# myfly.net
KiCad netlist of a schematic drawn in EasyEDA Pro
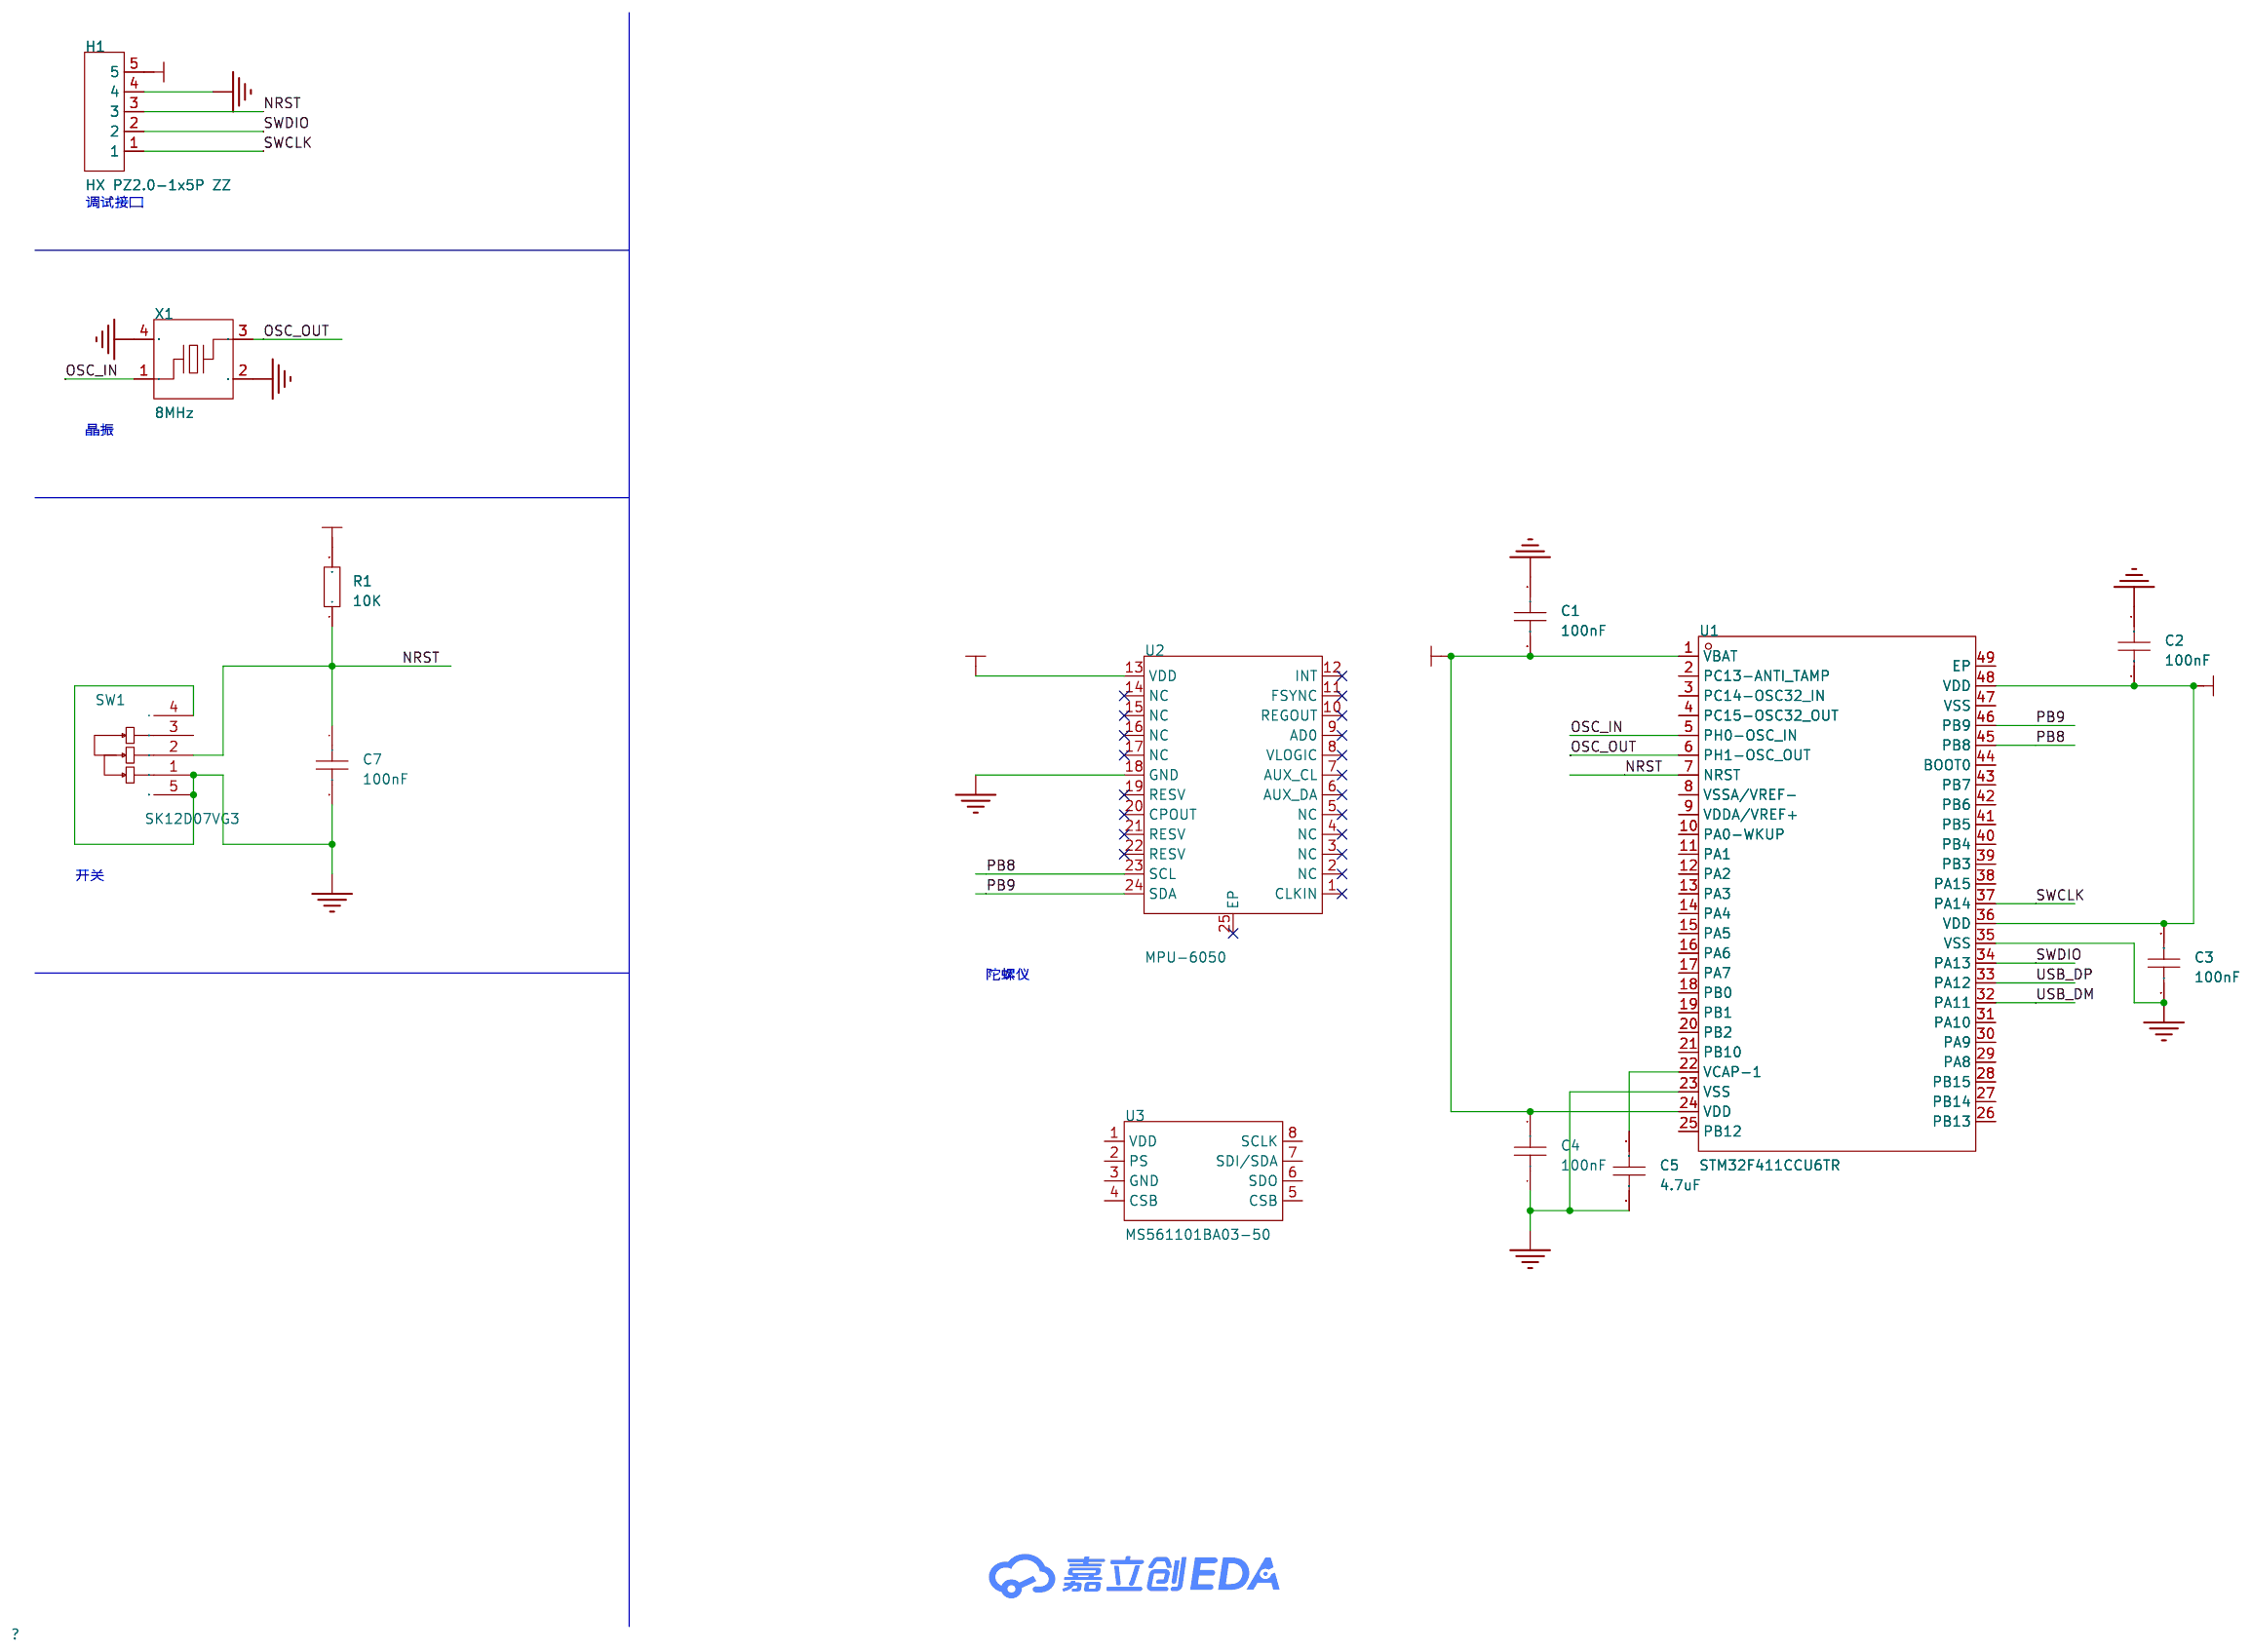
[diagram p0: P1]
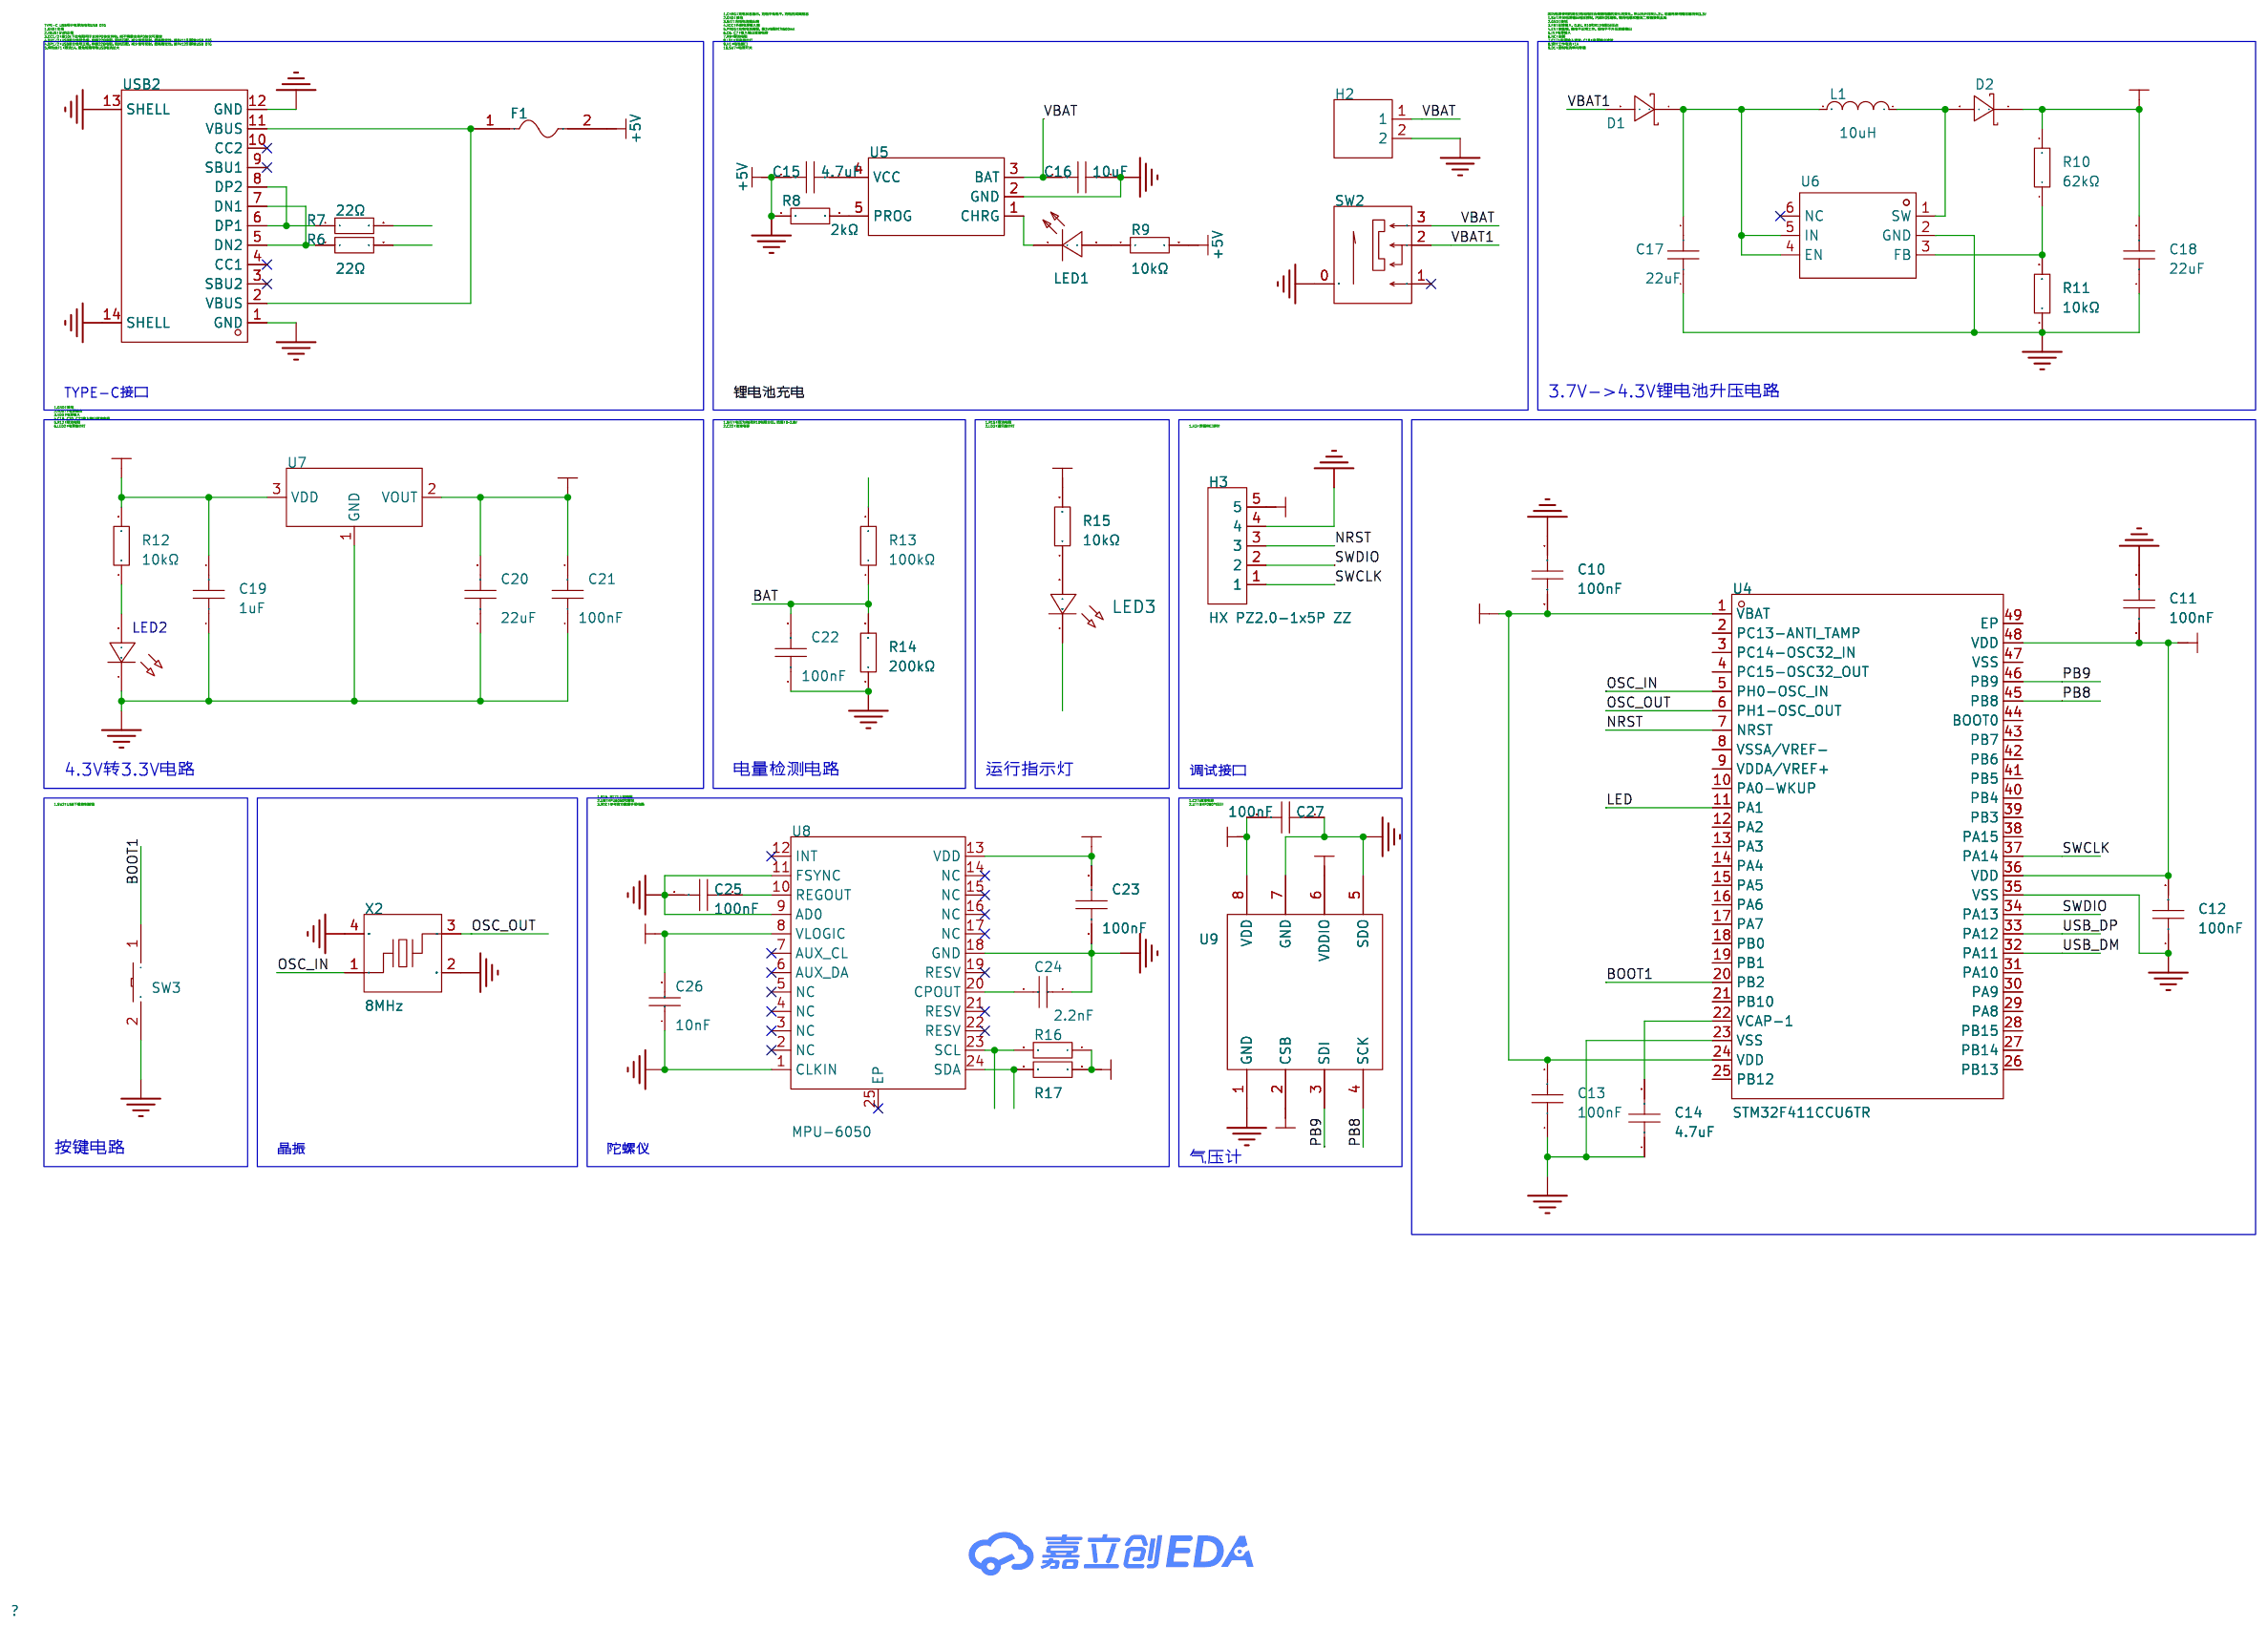
[diagram p1: P2]

(export (version "E")
  (design (tool "Eeschema 10.0.6"))
  (components
    (comp (ref "C1")
      (value "100nF")
      (footprint "easyedapro:C0402")
      (description "容值:100nF;精度:±5%;额定电压:25V;温度系数:X7R;")
      (fields
        (field (name "Manufacturer Part") "CGA0402X7R104J250GT")
        (field (name "Manufacturer") "HRE(芯声)")
      )
      (libsource (lib "easyedapro") (part "CGA0402X7R104J250GT"))
    )
    (comp (ref "C2")
      (value "100nF")
      (footprint "easyedapro:C0402")
      (description "容值:100nF;精度:±5%;额定电压:25V;温度系数:X7R;")
      (fields
        (field (name "Manufacturer Part") "CGA0402X7R104J250GT")
        (field (name "Manufacturer") "HRE(芯声)")
      )
      (libsource (lib "easyedapro") (part "CGA0402X7R104J250GT"))
    )
    (comp (ref "C3")
      (value "100nF")
      (footprint "easyedapro:C0402")
      (description "容值:100nF;精度:±5%;额定电压:25V;温度系数:X7R;")
      (fields
        (field (name "Manufacturer Part") "CGA0402X7R104J250GT")
        (field (name "Manufacturer") "HRE(芯声)")
      )
      (libsource (lib "easyedapro") (part "CGA0402X7R104J250GT"))
    )
    (comp (ref "C4")
      (value "100nF")
      (footprint "easyedapro:C0402")
      (description "容值:100nF;精度:±5%;额定电压:25V;温度系数:X7R;")
      (fields
        (field (name "Manufacturer Part") "CGA0402X7R104J250GT")
        (field (name "Manufacturer") "HRE(芯声)")
      )
      (libsource (lib "easyedapro") (part "CGA0402X7R104J250GT"))
    )
    (comp (ref "C5")
      (value "4.7uF")
      (footprint "easyedapro:C0402")
      (description "容值:4.7uF;精度:±10%;额定电压:6.3V;温度系数:X5R;")
      (fields
        (field (name "Manufacturer Part") "HGC0402R5475K6R3NTEJ")
        (field (name "Manufacturer") "Chinocera(华瓷)")
      )
      (libsource (lib "easyedapro") (part "HGC0402R5475K6R3NTEJ"))
    )
    (comp (ref "C7")
      (value "100nF")
      (footprint "easyedapro:C0402")
      (description "容值:100nF;精度:±5%;额定电压:25V;温度系数:X7R;")
      (fields
        (field (name "Manufacturer Part") "CGA0402X7R104J250GT")
        (field (name "Manufacturer") "HRE(芯声)")
      )
      (libsource (lib "easyedapro") (part "CGA0402X7R104J250GT"))
    )
    (comp (ref "H1")
      (value "HX PZ2.0-1x5P ZZ")
      (footprint "easyedapro:HDR-TH_5P-P2.00-V-M")
      (fields (field (name "Manufacturer") "hanxia(韩下)"))
      (libsource (lib "easyedapro") (part "HX PZ2.0-1X5P ZZ"))
    )
    (comp (ref "R1") (value "10K") (footprint "easyedapro:R0402") (libsource (lib "easyedapro") (part "电阻")))
    (comp (ref "SW1")
      (value "SK12D07VG3")
      (footprint "easyedapro:SW-TH_SK12D07VG3")
      (description "电路结构:单刀双掷;安装方式:-;开关颜色:-;额定电流:500mA;额定电压:50V;工作寿命:5千次;")
      (fields (field (name "Manufacturer") "SHOU HAN(首韩)"))
      (libsource (lib "easyedapro") (part "SK12D07VG3_C431547"))
    )
    (comp (ref "U1")
      (value "STM32F411CCU6TR")
      (footprint "easyedapro:QFN-48_L7.0-W7.0-P0.50-BL-EP5.1")
      (description "CPU内核:ARM-M4;CPU最大主频:100MHz;应用领域:-;")
      (fields (field (name "Manufacturer") "ST(意法半导体)"))
      (libsource (lib "easyedapro") (part "STM32F411CCU6TR"))
    )
    (comp (ref "U2")
      (value "MPU-6050")
      (footprint "easyedapro:QFN-24_L4.0-W4.0-P0.50-BL-EP2.7")
      (description "传感器类型:加速度计陀螺仪;")
      (fields (field (name "Manufacturer") "TDK InvenSense(应美盛)"))
      (libsource (lib "easyedapro") (part "MPU-6050_C24112"))
    )
    (comp (ref "U3")
      (value "MS561101BA03-50")
      (footprint "easyedapro:SENSORS-SMD_MS5611-01BA03")
      (description "压力范围:1Kpa~1.2bar;接口类型:SpI；I2C;")
      (fields (field (name "Manufacturer") "TE Connectivity(泰科电子)"))
      (libsource (lib "easyedapro") (part "MS561101BA03-50"))
    )
    (comp (ref "X1")
      (value "8MHz")
      (footprint "easyedapro:CRYSTAL-SMD_4P-L3.2-W2.5-BL")
      (description "晶振类型:贴片晶振;频率:8MHz;常温频差:±10ppm;负载电容:20pF;频率稳定度:±30ppm;")
      (fields
        (field (name "Manufacturer Part") "SX3B8.000F2010F30")
        (field (name "Manufacturer") "SCTF(星通时频)")
      )
      (libsource (lib "easyedapro") (part "SX3B8.000F2010F30"))
    )
    (comp (ref "C10")
      (value "100nF")
      (footprint "easyedapro:C0402")
      (description "容值:100nF;精度:±5%;额定电压:25V;温度系数:X7R;")
      (fields
        (field (name "Manufacturer Part") "CGA0402X7R104J250GT")
        (field (name "Manufacturer") "HRE(芯声)")
      )
      (libsource (lib "easyedapro") (part "CGA0402X7R104J250GT"))
    )
    (comp (ref "C11")
      (value "100nF")
      (footprint "easyedapro:C0402")
      (description "容值:100nF;精度:±5%;额定电压:25V;温度系数:X7R;")
      (fields
        (field (name "Manufacturer Part") "CGA0402X7R104J250GT")
        (field (name "Manufacturer") "HRE(芯声)")
      )
      (libsource (lib "easyedapro") (part "CGA0402X7R104J250GT"))
    )
    (comp (ref "C12")
      (value "100nF")
      (footprint "easyedapro:C0402")
      (description "容值:100nF;精度:±5%;额定电压:25V;温度系数:X7R;")
      (fields
        (field (name "Manufacturer Part") "CGA0402X7R104J250GT")
        (field (name "Manufacturer") "HRE(芯声)")
      )
      (libsource (lib "easyedapro") (part "CGA0402X7R104J250GT"))
    )
    (comp (ref "C13")
      (value "100nF")
      (footprint "easyedapro:C0402")
      (description "容值:100nF;精度:±5%;额定电压:25V;温度系数:X7R;")
      (fields
        (field (name "Manufacturer Part") "CGA0402X7R104J250GT")
        (field (name "Manufacturer") "HRE(芯声)")
      )
      (libsource (lib "easyedapro") (part "CGA0402X7R104J250GT"))
    )
    (comp (ref "C14")
      (value "4.7uF")
      (footprint "easyedapro:C0402")
      (description "容值:4.7uF;精度:±10%;额定电压:6.3V;温度系数:X5R;")
      (fields
        (field (name "Manufacturer Part") "HGC0402R5475K6R3NTEJ")
        (field (name "Manufacturer") "Chinocera(华瓷)")
      )
      (libsource (lib "easyedapro") (part "HGC0402R5475K6R3NTEJ"))
    )
    (comp (ref "C15")
      (value "4.7uF")
      (footprint "easyedapro:C0603")
      (description "容值:4.7uF;精度:±10%;额定电压:16V;温度系数:X5R;")
      (fields
        (field (name "Manufacturer Part") "CL10A475KO8NNNC")
        (field (name "Manufacturer") "SAMSUNG(三星)")
      )
      (libsource (lib "easyedapro") (part "CL10A475KO8NNNC"))
    )
    (comp (ref "C16")
      (value "10uF")
      (footprint "easyedapro:C0603")
      (description "容值:10uF;精度:±10%;额定电压:10V;温度系数:X5R;")
      (fields
        (field (name "Manufacturer Part") "CL10A106KP8NNNC")
        (field (name "Manufacturer") "SAMSUNG(三星)")
      )
      (libsource (lib "easyedapro") (part "CL10A106KP8NNNC"))
    )
    (comp (ref "C17")
      (value "22uF")
      (footprint "easyedapro:C0805")
      (description "容值:22uF;精度:±20%;额定电压:25V;温度系数:X5R;")
      (fields
        (field (name "Manufacturer Part") "CL21A226MAQNNNE")
        (field (name "Manufacturer") "SAMSUNG(三星)")
      )
      (libsource (lib "easyedapro") (part "CL21A226MAQNNNE"))
    )
    (comp (ref "C18")
      (value "22uF")
      (footprint "easyedapro:C0805")
      (description "容值:22uF;精度:±20%;额定电压:25V;温度系数:X5R;")
      (fields
        (field (name "Manufacturer Part") "CL21A226MAQNNNE")
        (field (name "Manufacturer") "SAMSUNG(三星)")
      )
      (libsource (lib "easyedapro") (part "CL21A226MAQNNNE"))
    )
    (comp (ref "C19")
      (value "1uF")
      (footprint "easyedapro:C0603")
      (description "容值:1uF;精度:±10%;额定电压:50V;温度系数:X5R;")
      (fields
        (field (name "Manufacturer Part") "CL10A105KB8NNNC")
        (field (name "Manufacturer") "SAMSUNG(三星)")
      )
      (libsource (lib "easyedapro") (part "CL10A105KB8NNNC"))
    )
    (comp (ref "C20")
      (value "22uF")
      (footprint "easyedapro:C0603")
      (description "容值:22uF;精度:±20%;额定电压:6.3V;温度系数:X5R;")
      (fields
        (field (name "Manufacturer Part") "CL10A226MQ8NRNC")
        (field (name "Manufacturer") "SAMSUNG(三星)")
      )
      (libsource (lib "easyedapro") (part "CL10A226MQ8NRNC"))
    )
    (comp (ref "C21")
      (value "100nF")
      (footprint "easyedapro:C0603")
      (description "容值:100nF;精度:±10%;额定电压:50V;温度系数:X7R;")
      (fields
        (field (name "Manufacturer Part") "CL10B104KB8NNNC")
        (field (name "Manufacturer") "SAMSUNG(三星)")
      )
      (libsource (lib "easyedapro") (part "CL10B104KB8NNNC"))
    )
    (comp (ref "C22")
      (value "100nF")
      (footprint "easyedapro:C0603")
      (description "容值:100nF;精度:±10%;额定电压:50V;温度系数:X7R;")
      (fields
        (field (name "Manufacturer Part") "CL10B104KB8NNNC")
        (field (name "Manufacturer") "SAMSUNG(三星)")
      )
      (libsource (lib "easyedapro") (part "CL10B104KB8NNNC"))
    )
    (comp (ref "C23")
      (value "100nF")
      (footprint "easyedapro:C0603")
      (description "容值:100nF;精度:±10%;额定电压:50V;温度系数:X7R;")
      (fields
        (field (name "Manufacturer Part") "CL10B104KB8NNNC")
        (field (name "Manufacturer") "SAMSUNG(三星)")
      )
      (libsource (lib "easyedapro") (part "CL10B104KB8NNNC"))
    )
    (comp (ref "C24")
      (value "2.2nF")
      (footprint "easyedapro:C0603")
      (description "容值:2.2nF;精度:±10%;额定电压:50V;温度系数:X7R;")
      (fields
        (field (name "Manufacturer Part") "CL10B222KB8NNNC")
        (field (name "Manufacturer") "SAMSUNG(三星)")
      )
      (libsource (lib "easyedapro") (part "CL10B222KB8NNNC"))
    )
    (comp (ref "C25")
      (value "100nF")
      (footprint "easyedapro:C0603")
      (description "容值:100nF;精度:±10%;额定电压:50V;温度系数:X7R;")
      (fields
        (field (name "Manufacturer Part") "CL10B104KB8NNNC")
        (field (name "Manufacturer") "SAMSUNG(三星)")
      )
      (libsource (lib "easyedapro") (part "CL10B104KB8NNNC"))
    )
    (comp (ref "C26")
      (value "10nF")
      (footprint "easyedapro:C0603")
      (description "容值:10nF;精度:±10%;额定电压:50V;温度系数:X7R;")
      (fields
        (field (name "Manufacturer Part") "CL10B103KB8NNNC")
        (field (name "Manufacturer") "SAMSUNG(三星)")
      )
      (libsource (lib "easyedapro") (part "CL10B103KB8NNNC"))
    )
    (comp (ref "C27")
      (value "100nF")
      (footprint "easyedapro:C0603")
      (description "容值:100nF;精度:±10%;额定电压:50V;温度系数:X7R;")
      (fields
        (field (name "Manufacturer Part") "CL10B104KB8NNNC")
        (field (name "Manufacturer") "SAMSUNG(三星)")
      )
      (libsource (lib "easyedapro") (part "CL10B104KB8NNNC"))
    )
    (comp (ref "D1")
      (value "1N5819WS")
      (footprint "easyedapro:SOD-323_L1.8-W1.3-LS2.5-RD")
      (description "正向压降(Vf):600mV@1A;直流反向耐压(Vr):40V;整流电流:1A;")
      (fields (field (name "Manufacturer") "Hottech(合科泰)"))
      (libsource (lib "easyedapro") (part "1N5819WS"))
    )
    (comp (ref "D2")
      (value "1N5819WS")
      (footprint "easyedapro:SOD-323_L1.8-W1.3-LS2.5-RD")
      (description "正向压降(Vf):600mV@1A;直流反向耐压(Vr):40V;整流电流:1A;")
      (fields (field (name "Manufacturer") "Hottech(合科泰)"))
      (libsource (lib "easyedapro") (part "1N5819WS"))
    )
    (comp (ref "F1")
      (value "JK-nSMD100/16V")
      (footprint "easyedapro:F1206")
      (description "耐压:16V;最大电流:100A;保持电流(Ih):1A;跳闸电流:1.8A;")
      (fields (field (name "Manufacturer") "JK(金科)"))
      (libsource (lib "easyedapro") (part "JK-NSMD100/16V"))
    )
    (comp (ref "H2")
      (value "B-2100S02P-A110")
      (footprint "easyedapro:HDR-TH_2P-P2.54-V-M-1")
      (fields (field (name "Manufacturer") "Ckmtw(灿科盟)"))
      (libsource (lib "easyedapro") (part "210S-1*2P L=11.6MMGold-plated black"))
    )
    (comp (ref "H3")
      (value "HX PZ2.0-1x5P ZZ")
      (footprint "easyedapro:HDR-TH_5P-P2.00-V-M")
      (fields (field (name "Manufacturer") "hanxia(韩下)"))
      (libsource (lib "easyedapro") (part "HX PZ2.0-1X5P ZZ"))
    )
    (comp (ref "L1")
      (value "10uH")
      (footprint "easyedapro:IND-SMD_L2.5-W2.0")
      (description "电感值:10uH;精度:±20%;额定电流:1.2A;饱和电流(Isat):1.6A;类型:一体成型电感;")
      (fields
        (field (name "Manufacturer Part") "FTC252012S100MBCA")
        (field (name "Manufacturer") "cjiang(长江微电)")
      )
      (libsource (lib "easyedapro") (part "FTC252012S100MBCA"))
    )
    (comp (ref "LED1")
      (value "KT-0603R")
      (footprint "easyedapro:LED0603-RD")
      (description "发光颜色:红色;功率:-;正向电流:-;主波长:-;二极管配置:-;透镜颜色:-;色温:-;发光角度:-;载带方式:-;工作温度:-40°C~+85°C;")
      (fields (field (name "Manufacturer") "KENTO"))
      (libsource (lib "easyedapro") (part "KT-0603R"))
    )
    (comp (ref "LED2")
      (value "~")
      (footprint "easyedapro:LED_0603")
      (libsource (lib "easyedapro") (part "LED_G"))
    )
    (comp (ref "LED3")
      (value "~")
      (footprint "easyedapro:LED_0603")
      (libsource (lib "easyedapro") (part "LED_R"))
    )
    (comp (ref "R6")
      (value "22Ω")
      (footprint "easyedapro:R0603")
      (description "电阻类型:厚膜电阻;阻值:22Ω;精度:±1%;功率:100mW;最大工作电压:75V;温度系数:±100ppm/°C;")
      (fields
        (field (name "Manufacturer Part") "0603WAF220JT5E")
        (field (name "Manufacturer") "UNI-ROYAL(厚声)")
      )
      (libsource (lib "easyedapro") (part "0603WAF220JT5E"))
    )
    (comp (ref "R7")
      (value "22Ω")
      (footprint "easyedapro:R0603")
      (description "电阻类型:厚膜电阻;阻值:22Ω;精度:±1%;功率:100mW;最大工作电压:75V;温度系数:±100ppm/°C;")
      (fields
        (field (name "Manufacturer Part") "0603WAF220JT5E")
        (field (name "Manufacturer") "UNI-ROYAL(厚声)")
      )
      (libsource (lib "easyedapro") (part "0603WAF220JT5E"))
    )
    (comp (ref "R8")
      (value "2kΩ")
      (footprint "easyedapro:R0603")
      (description "电阻类型:厚膜电阻;阻值:2kΩ;精度:±1%;功率:100mW;工作电压:75V;温度系数:±100ppm/°C;")
      (fields
        (field (name "Manufacturer Part") "0603WAF2001T5E")
        (field (name "Manufacturer") "UNI-ROYAL(厚声)")
      )
      (libsource (lib "easyedapro") (part "0603WAF2001T5E"))
    )
    (comp (ref "R9")
      (value "10kΩ")
      (footprint "easyedapro:R0603")
      (description "电阻类型:厚膜电阻;阻值:10kΩ;精度:±1%;功率:100mW;工作电压:75V;温度系数:±100ppm/°C;")
      (fields
        (field (name "Manufacturer Part") "0603WAF1002T5E")
        (field (name "Manufacturer") "UNI-ROYAL(厚声)")
      )
      (libsource (lib "easyedapro") (part "0603WAF1002T5E"))
    )
    (comp (ref "R10")
      (value "62kΩ")
      (footprint "easyedapro:R0603")
      (description "电阻类型:厚膜电阻;阻值:62kΩ;精度:±1%;功率:100mW;工作电压:75V;温度系数:±100ppm/°C;")
      (fields
        (field (name "Manufacturer Part") "0603WAF6202T5E")
        (field (name "Manufacturer") "UNI-ROYAL(厚声)")
      )
      (libsource (lib "easyedapro") (part "0603WAF6202T5E"))
    )
    (comp (ref "R11")
      (value "10kΩ")
      (footprint "easyedapro:R0603")
      (description "电阻类型:厚膜电阻;阻值:10kΩ;精度:±1%;功率:100mW;工作电压:75V;温度系数:±100ppm/°C;")
      (fields
        (field (name "Manufacturer Part") "0603WAF1002T5E")
        (field (name "Manufacturer") "UNI-ROYAL(厚声)")
      )
      (libsource (lib "easyedapro") (part "0603WAF1002T5E"))
    )
    (comp (ref "R12")
      (value "10kΩ")
      (footprint "easyedapro:R0603")
      (description "电阻类型:厚膜电阻;阻值:10kΩ;精度:±1%;功率:100mW;工作电压:75V;温度系数:±100ppm/°C;")
      (fields
        (field (name "Manufacturer Part") "0603WAF1002T5E")
        (field (name "Manufacturer") "UNI-ROYAL(厚声)")
      )
      (libsource (lib "easyedapro") (part "0603WAF1002T5E"))
    )
    (comp (ref "R13")
      (value "100kΩ")
      (footprint "easyedapro:R0603")
      (description "电阻类型:厚膜电阻;阻值:100kΩ;精度:±1%;功率:100mW;工作电压:75V;温度系数:±100ppm/°C;")
      (fields
        (field (name "Manufacturer Part") "0603WAF1003T5E")
        (field (name "Manufacturer") "UNI-ROYAL(厚声)")
      )
      (libsource (lib "easyedapro") (part "0603WAF1003T5E"))
    )
    (comp (ref "R14")
      (value "200kΩ")
      (footprint "easyedapro:R0603")
      (description "电阻类型:厚膜电阻;阻值:200kΩ;精度:±1%;功率:100mW;最大工作电压:75V;温度系数:±100ppm/°C;")
      (fields
        (field (name "Manufacturer Part") "0603WAF2003T5E")
        (field (name "Manufacturer") "UNI-ROYAL(厚声)")
      )
      (libsource (lib "easyedapro") (part "0603WAF2003T5E"))
    )
    (comp (ref "R15")
      (value "10kΩ")
      (footprint "easyedapro:R0603")
      (description "电阻类型:厚膜电阻;阻值:10kΩ;精度:±1%;功率:100mW;工作电压:75V;温度系数:±100ppm/°C;")
      (fields
        (field (name "Manufacturer Part") "0603WAF1002T5E")
        (field (name "Manufacturer") "UNI-ROYAL(厚声)")
      )
      (libsource (lib "easyedapro") (part "0603WAF1002T5E"))
    )
    (comp (ref "R16")
      (value "4.7kΩ")
      (footprint "easyedapro:R0603")
      (description "电阻类型:厚膜电阻;阻值:4.7kΩ;精度:±1%;功率:100mW;工作电压:75V;温度系数:±100ppm/°C;")
      (fields
        (field (name "Manufacturer Part") "0603WAF4701T5E")
        (field (name "Manufacturer") "UNI-ROYAL(厚声)")
      )
      (libsource (lib "easyedapro") (part "0603WAF4701T5E"))
    )
    (comp (ref "R17")
      (value "4.7kΩ")
      (footprint "easyedapro:R0603")
      (description "电阻类型:厚膜电阻;阻值:4.7kΩ;精度:±1%;功率:100mW;工作电压:75V;温度系数:±100ppm/°C;")
      (fields
        (field (name "Manufacturer Part") "0603WAF4701T5E")
        (field (name "Manufacturer") "UNI-ROYAL(厚声)")
      )
      (libsource (lib "easyedapro") (part "0603WAF4701T5E"))
    )
    (comp (ref "SW2")
      (value "SK-3296S-01-L1")
      (footprint "easyedapro:SW-SMD_3P-P1.50_L2.7-W6.6")
      (description "电路结构:单刀双掷;安装方式:卧贴;开关颜色:黑色;额定电流:50mA;额定电压:12V;工作寿命:1万次;")
      (fields (field (name "Manufacturer") "XKB Connection(中国星坤)"))
      (libsource (lib "easyedapro") (part "SK-3296S-01-L1"))
    )
    (comp (ref "SW3")
      (value "TS-1101-C-W")
      (footprint "easyedapro:SW-SMD_L6.0-W3.3-LS8.0")
      (fields (field (name "Manufacturer") "XKB Connectivity(中国星坤)"))
      (libsource (lib "easyedapro") (part "TS-1101-C-W"))
    )
    (comp (ref "U4")
      (value "STM32F411CCU6TR")
      (footprint "easyedapro:QFN-48_L7.0-W7.0-P0.50-BL-EP5.1")
      (description "CPU内核:ARM-M4;CPU最大主频:100MHz;应用领域:-;")
      (fields (field (name "Manufacturer") "ST(意法半导体)"))
      (libsource (lib "easyedapro") (part "STM32F411CCU6TR"))
    )
    (comp (ref "U5")
      (value "LTH7")
      (footprint "easyedapro:SOT-23-5_L2.9-W1.6-P0.95-LS2.8-BR")
      (fields (field (name "Manufacturer") "TECH PUBLIC(台舟)"))
      (libsource (lib "easyedapro") (part "LTH7_C5342381"))
    )
    (comp (ref "U6")
      (value "MT3608")
      (footprint "easyedapro:SOT-23-6_L2.9-W1.6-P0.95-LS2.8-BL")
      (description "功能类型:升压型;输出类型:可调;工作电压:2V~24V;输出电压:-;输出电流:2A;")
      (fields (field (name "Manufacturer") "西安航天民芯"))
      (libsource (lib "easyedapro") (part "MT3608"))
    )
    (comp (ref "U7")
      (value "662K")
      (footprint "easyedapro:SOT-23-3_L2.9-W1.3-P1.90-LS2.4-BR")
      (description "输出类型:固定;工作电压:8V;输出电压:3.3V;输出电流:300mA;电源纹波抑制比(PSRR):40dB@(1kHz);输出极性:正极;")
      (fields (field (name "Manufacturer") "HXY MOSFET(华轩阳电子)"))
      (libsource (lib "easyedapro") (part "662K"))
    )
    (comp (ref "U8")
      (value "MPU-6050")
      (footprint "easyedapro:QFN-24_L4.0-W4.0-P0.50-BL-EP2.7")
      (description "传感器类型:加速度计陀螺仪;")
      (fields (field (name "Manufacturer") "TDK InvenSense(应美盛)"))
      (libsource (lib "easyedapro") (part "MPU-6050_C24112"))
    )
    (comp (ref "U9")
      (value "BMP280")
      (footprint "easyedapro:LGA-8_L2.5-W2.0-P0.65_AMP6127")
      (description "Bosch气压传感器新品，可测量大气压力，带高精度温度测量，可校准精确计算海拔高度。I2C或SPI接口，宽量程（300-1100hpa），精度高")
      (fields (field (name "Manufacturer") "Bosch(博世)"))
      (libsource (lib "easyedapro") (part "BMP280"))
    )
    (comp (ref "USB2")
      (value "TYPE-C 16PIN 2MD(073)")
      (footprint "easyedapro:USB-C-SMD_TYPE-C-6PIN-2MD-073")
      (description "连接器类型:Type-C;协议标准:-;公母:母;安装方式:卧贴;触点数量:16P;端口数量:1;额定电流 - 电源:3A;工作温度:-25°C~+85°C;")
      (fields (field (name "Manufacturer") "SHOU HAN(首韩)"))
      (libsource (lib "easyedapro") (part "TYPE-C 16PIN 2MD(073)"))
    )
    (comp (ref "X2")
      (value "8MHz")
      (footprint "easyedapro:CRYSTAL-SMD_4P-L3.2-W2.5-BL")
      (description "晶振类型:贴片晶振;频率:8MHz;常温频差:±10ppm;负载电容:20pF;频率稳定度:±30ppm;")
      (fields
        (field (name "Manufacturer Part") "SX3B8.000F2010F30")
        (field (name "Manufacturer") "SCTF(星通时频)")
      )
      (libsource (lib "easyedapro") (part "SX3B8.000F2010F30"))
    )
  )
  (nets
    (net (code "1") (name "+3.3V") (class "Default")
      (node (ref "C10") (pin "2") (pinfunction "2_2") (pintype "unspecified"))
      (node (ref "C11") (pin "2") (pinfunction "2_2") (pintype "unspecified"))
      (node (ref "C12") (pin "2") (pinfunction "2_2") (pintype "unspecified"))
      (node (ref "C13") (pin "2") (pinfunction "2_2") (pintype "unspecified"))
      (node (ref "C20") (pin "2") (pinfunction "2_2") (pintype "unspecified"))
      (node (ref "C21") (pin "2") (pinfunction "2_2") (pintype "unspecified"))
      (node (ref "C23") (pin "1") (pinfunction "1_1") (pintype "unspecified"))
      (node (ref "C23") (pin "2") (pinfunction "2_2") (pintype "unspecified"))
      (node (ref "C24") (pin "2") (pinfunction "2_2") (pintype "input"))
      (node (ref "C26") (pin "2") (pinfunction "2_2") (pintype "input"))
      (node (ref "C27") (pin "2") (pinfunction "2_2") (pintype "unspecified"))
      (node (ref "H3") (pin "5") (pinfunction "5_5") (pintype "unspecified"))
      (node (ref "R15") (pin "2") (pinfunction "2_2") (pintype "input"))
      (node (ref "R16") (pin "1") (pinfunction "1_1") (pintype "input"))
      (node (ref "R17") (pin "1") (pinfunction "1_1") (pintype "input"))
      (node (ref "U4") (pin "1") (pinfunction "VBAT_1") (pintype "unspecified"))
      (node (ref "U4") (pin "24") (pinfunction "VDD_24") (pintype "unspecified"))
      (node (ref "U4") (pin "36") (pinfunction "VDD_36") (pintype "unspecified"))
      (node (ref "U4") (pin "48") (pinfunction "VDD_48") (pintype "unspecified"))
      (node (ref "U7") (pin "2") (pinfunction "VOUT_2") (pintype "unspecified"))
      (node (ref "U8") (pin "13") (pinfunction "VDD_13") (pintype "unspecified"))
      (node (ref "U8") (pin "18") (pinfunction "GND_18") (pintype "unspecified"))
      (node (ref "U8") (pin "8") (pinfunction "VLOGIC_8") (pintype "unspecified"))
      (node (ref "U9") (pin "2") (pinfunction "CSB_2") (pintype "unspecified"))
      (node (ref "U9") (pin "6") (pinfunction "VDDIO_6") (pintype "unspecified"))
      (node (ref "U9") (pin "8") (pinfunction "VDD_8") (pintype "unspecified"))
    )
    (net (code "2") (name "+4.3V") (class "Default")
      (node (ref "C18") (pin "2") (pinfunction "2_2") (pintype "unspecified"))
      (node (ref "C19") (pin "2") (pinfunction "2_2") (pintype "unspecified"))
      (node (ref "D2") (pin "1") (pinfunction "K_1") (pintype "unspecified"))
      (node (ref "R10") (pin "2") (pinfunction "2_2") (pintype "input"))
      (node (ref "R12") (pin "2") (pinfunction "2_2") (pintype "input"))
      (node (ref "U7") (pin "3") (pinfunction "VDD_3") (pintype "unspecified"))
    )
    (net (code "3") (name "+5V") (class "Default")
      (node (ref "C15") (pin "1") (pinfunction "1_1") (pintype "unspecified"))
      (node (ref "F1") (pin "2") (pinfunction "2_2") (pintype "unspecified"))
      (node (ref "R8") (pin "1") (pinfunction "1_1") (pintype "input"))
      (node (ref "R9") (pin "2") (pinfunction "2_2") (pintype "input"))
    )
    (net (code "4") (name "3V3_1") (class "Default")
      (node (ref "C1") (pin "2") (pinfunction "2_2") (pintype "unspecified"))
      (node (ref "C2") (pin "2") (pinfunction "2_2") (pintype "unspecified"))
      (node (ref "C3") (pin "2") (pinfunction "2_2") (pintype "unspecified"))
      (node (ref "C4") (pin "2") (pinfunction "2_2") (pintype "unspecified"))
      (node (ref "H1") (pin "5") (pinfunction "5_5") (pintype "unspecified"))
      (node (ref "R1") (pin "2") (pinfunction "2_2") (pintype "input"))
      (node (ref "U1") (pin "1") (pinfunction "VBAT_1") (pintype "unspecified"))
      (node (ref "U1") (pin "24") (pinfunction "VDD_24") (pintype "unspecified"))
      (node (ref "U1") (pin "36") (pinfunction "VDD_36") (pintype "unspecified"))
      (node (ref "U1") (pin "48") (pinfunction "VDD_48") (pintype "unspecified"))
      (node (ref "U2") (pin "13") (pinfunction "VDD_13") (pintype "unspecified"))
    )
    (net (code "5") (name "BAT") (class "Default")
      (node (ref "C22") (pin "2") (pinfunction "2_2") (pintype "unspecified"))
      (node (ref "R13") (pin "1") (pinfunction "1_1") (pintype "input"))
      (node (ref "R14") (pin "2") (pinfunction "2_2") (pintype "input"))
    )
    (net (code "6") (name "BOOT1") (class "Default")
      (node (ref "SW3") (pin "1") (pinfunction "1_1") (pintype "unspecified"))
      (node (ref "U4") (pin "20") (pinfunction "PB2_20") (pintype "unspecified"))
    )
    (net (code "7") (name "GND") (class "Default")
      (node (ref "C1") (pin "1") (pinfunction "1_1") (pintype "unspecified"))
      (node (ref "C10") (pin "1") (pinfunction "1_1") (pintype "unspecified"))
      (node (ref "C11") (pin "1") (pinfunction "1_1") (pintype "unspecified"))
      (node (ref "C12") (pin "1") (pinfunction "1_1") (pintype "unspecified"))
      (node (ref "C13") (pin "1") (pinfunction "1_1") (pintype "unspecified"))
      (node (ref "C14") (pin "1") (pinfunction "1_1") (pintype "unspecified"))
      (node (ref "C16") (pin "2") (pinfunction "2_2") (pintype "unspecified"))
      (node (ref "C17") (pin "1") (pinfunction "1_1") (pintype "unspecified"))
      (node (ref "C18") (pin "1") (pinfunction "1_1") (pintype "unspecified"))
      (node (ref "C19") (pin "1") (pinfunction "1_1") (pintype "unspecified"))
      (node (ref "C2") (pin "1") (pinfunction "1_1") (pintype "unspecified"))
      (node (ref "C20") (pin "1") (pinfunction "1_1") (pintype "unspecified"))
      (node (ref "C21") (pin "1") (pinfunction "1_1") (pintype "unspecified"))
      (node (ref "C22") (pin "1") (pinfunction "1_1") (pintype "unspecified"))
      (node (ref "C25") (pin "2") (pinfunction "2_2") (pintype "unspecified"))
      (node (ref "C26") (pin "1") (pinfunction "1_1") (pintype "input"))
      (node (ref "C27") (pin "1") (pinfunction "1_1") (pintype "unspecified"))
      (node (ref "C3") (pin "1") (pinfunction "1_1") (pintype "unspecified"))
      (node (ref "C4") (pin "1") (pinfunction "1_1") (pintype "unspecified"))
      (node (ref "C5") (pin "1") (pinfunction "1_1") (pintype "unspecified"))
      (node (ref "C7") (pin "2") (pinfunction "2_2") (pintype "unspecified"))
      (node (ref "H1") (pin "4") (pinfunction "4_4") (pintype "unspecified"))
      (node (ref "H2") (pin "2") (pinfunction "2_2") (pintype "unspecified"))
      (node (ref "H3") (pin "4") (pinfunction "4_4") (pintype "unspecified"))
      (node (ref "LED2") (pin "1") (pinfunction "C_1") (pintype "input"))
      (node (ref "R11") (pin "1") (pinfunction "1_1") (pintype "input"))
      (node (ref "R14") (pin "1") (pinfunction "1_1") (pintype "input"))
      (node (ref "SW1") (pin "1") (pinfunction "1_1") (pintype "unspecified"))
      (node (ref "SW1") (pin "4") (pinfunction "4_4") (pintype "unspecified"))
      (node (ref "SW1") (pin "5") (pinfunction "5_5") (pintype "unspecified"))
      (node (ref "SW2") (pin "0") (pinfunction "0_0") (pintype "unspecified"))
      (node (ref "SW3") (pin "2") (pinfunction "2_2") (pintype "unspecified"))
      (node (ref "U1") (pin "23") (pinfunction "VSS_23") (pintype "unspecified"))
      (node (ref "U1") (pin "35") (pinfunction "VSS_35") (pintype "unspecified"))
      (node (ref "U2") (pin "18") (pinfunction "GND_18") (pintype "unspecified"))
      (node (ref "U4") (pin "23") (pinfunction "VSS_23") (pintype "unspecified"))
      (node (ref "U4") (pin "35") (pinfunction "VSS_35") (pintype "unspecified"))
      (node (ref "U5") (pin "2") (pinfunction "GND_2") (pintype "unspecified"))
      (node (ref "U6") (pin "2") (pinfunction "GND_2") (pintype "unspecified"))
      (node (ref "U7") (pin "1") (pinfunction "GND_1") (pintype "unspecified"))
      (node (ref "U8") (pin "1") (pinfunction "CLKIN_1") (pintype "unspecified"))
      (node (ref "U8") (pin "11") (pinfunction "FSYNC_11") (pintype "unspecified"))
      (node (ref "U8") (pin "9") (pinfunction "AD0_9") (pintype "unspecified"))
      (node (ref "U9") (pin "1") (pinfunction "GND_1") (pintype "unspecified"))
      (node (ref "U9") (pin "5") (pinfunction "SDO_5") (pintype "unspecified"))
      (node (ref "U9") (pin "7") (pinfunction "GND_7") (pintype "unspecified"))
      (node (ref "USB2") (pin "1") (pinfunction "GND_1") (pintype "unspecified"))
      (node (ref "USB2") (pin "12") (pinfunction "GND_12") (pintype "unspecified"))
      (node (ref "USB2") (pin "13") (pinfunction "SHELL_13") (pintype "unspecified"))
      (node (ref "USB2") (pin "14") (pinfunction "SHELL_14") (pintype "unspecified"))
      (node (ref "X1") (pin "2") (pinfunction "GND_2") (pintype "input"))
      (node (ref "X1") (pin "4") (pinfunction "GND_4") (pintype "input"))
      (node (ref "X2") (pin "2") (pinfunction "GND_2") (pintype "input"))
      (node (ref "X2") (pin "4") (pinfunction "GND_4") (pintype "input"))
    )
    (net (code "8") (name "LED") (class "Default")
      (node (ref "U4") (pin "11") (pinfunction "PA1_11") (pintype "unspecified"))
    )
    (net (code "9") (name "NRST") (class "Default")
      (node (ref "C7") (pin "1") (pinfunction "1_1") (pintype "unspecified"))
      (node (ref "H1") (pin "3") (pinfunction "3_3") (pintype "unspecified"))
      (node (ref "H3") (pin "3") (pinfunction "3_3") (pintype "unspecified"))
      (node (ref "R1") (pin "1") (pinfunction "1_1") (pintype "input"))
      (node (ref "SW1") (pin "2") (pinfunction "2_2") (pintype "unspecified"))
      (node (ref "U1") (pin "7") (pinfunction "NRST_7") (pintype "unspecified"))
      (node (ref "U4") (pin "7") (pinfunction "NRST_7") (pintype "unspecified"))
    )
    (net (code "10") (name "Net-(D1-K)") (class "Default")
      (node (ref "C17") (pin "2") (pinfunction "2_2") (pintype "unspecified"))
      (node (ref "D1") (pin "1") (pinfunction "K_1") (pintype "unspecified"))
      (node (ref "L1") (pin "2") (pinfunction "2_2") (pintype "unspecified"))
      (node (ref "U6") (pin "4") (pinfunction "EN_4") (pintype "unspecified"))
      (node (ref "U6") (pin "5") (pinfunction "IN_5") (pintype "unspecified"))
    )
    (net (code "11") (name "Net-(D2-A)") (class "Default")
      (node (ref "D2") (pin "2") (pinfunction "A_2") (pintype "unspecified"))
      (node (ref "L1") (pin "1") (pinfunction "1_1") (pintype "unspecified"))
      (node (ref "U6") (pin "1") (pinfunction "SW_1") (pintype "unspecified"))
    )
    (net (code "12") (name "Net-(F1-Pad1)") (class "Default")
      (node (ref "F1") (pin "1") (pinfunction "1_1") (pintype "unspecified"))
      (node (ref "USB2") (pin "11") (pinfunction "VBUS_11") (pintype "unspecified"))
      (node (ref "USB2") (pin "2") (pinfunction "VBUS_2") (pintype "unspecified"))
    )
    (net (code "13") (name "Net-(LED1-A)") (class "Default")
      (node (ref "LED1") (pin "2") (pinfunction "A_2") (pintype "unspecified"))
      (node (ref "R9") (pin "1") (pinfunction "1_1") (pintype "input"))
    )
    (net (code "14") (name "Net-(LED1-K)") (class "Default")
      (node (ref "LED1") (pin "1") (pinfunction "K_1") (pintype "unspecified"))
      (node (ref "U5") (pin "1") (pinfunction "CHRG_1") (pintype "unspecified"))
    )
    (net (code "15") (name "Net-(LED2-A)") (class "Default")
      (node (ref "LED2") (pin "2") (pinfunction "A_2") (pintype "input"))
      (node (ref "R12") (pin "1") (pinfunction "1_1") (pintype "input"))
    )
    (net (code "16") (name "Net-(LED3-A)") (class "Default")
      (node (ref "LED3") (pin "2") (pinfunction "A_2") (pintype "input"))
      (node (ref "R15") (pin "1") (pinfunction "1_1") (pintype "input"))
    )
    (net (code "17") (name "Net-(U1-VCAP-1)") (class "Default")
      (node (ref "C5") (pin "2") (pinfunction "2_2") (pintype "unspecified"))
      (node (ref "U1") (pin "22") (pinfunction "VCAP-1_22") (pintype "unspecified"))
    )
    (net (code "18") (name "Net-(U4-VCAP-1)") (class "Default")
      (node (ref "C14") (pin "2") (pinfunction "2_2") (pintype "unspecified"))
      (node (ref "U4") (pin "22") (pinfunction "VCAP-1_22") (pintype "unspecified"))
    )
    (net (code "19") (name "Net-(U5-PROG)") (class "Default")
      (node (ref "R8") (pin "2") (pinfunction "2_2") (pintype "input"))
      (node (ref "U5") (pin "5") (pinfunction "PROG_5") (pintype "unspecified"))
    )
    (net (code "20") (name "Net-(U5-VCC)") (class "Default")
      (node (ref "C15") (pin "2") (pinfunction "2_2") (pintype "unspecified"))
      (node (ref "U5") (pin "4") (pinfunction "VCC_4") (pintype "unspecified"))
    )
    (net (code "21") (name "Net-(U6-FB)") (class "Default")
      (node (ref "R10") (pin "1") (pinfunction "1_1") (pintype "input"))
      (node (ref "R11") (pin "2") (pinfunction "2_2") (pintype "input"))
      (node (ref "U6") (pin "3") (pinfunction "FB_3") (pintype "unspecified"))
    )
    (net (code "22") (name "Net-(U8-CPOUT)") (class "Default")
      (node (ref "C24") (pin "1") (pinfunction "1_1") (pintype "input"))
      (node (ref "U8") (pin "20") (pinfunction "CPOUT_20") (pintype "unspecified"))
    )
    (net (code "23") (name "Net-(U8-REGOUT)") (class "Default")
      (node (ref "C25") (pin "1") (pinfunction "1_1") (pintype "unspecified"))
      (node (ref "U8") (pin "10") (pinfunction "REGOUT_10") (pintype "unspecified"))
    )
    (net (code "24") (name "Net-(U8-SCL)") (class "Default")
      (node (ref "R16") (pin "2") (pinfunction "2_2") (pintype "input"))
      (node (ref "U8") (pin "23") (pinfunction "SCL_23") (pintype "unspecified"))
    )
    (net (code "25") (name "Net-(U8-SDA)") (class "Default")
      (node (ref "R17") (pin "2") (pinfunction "2_2") (pintype "input"))
      (node (ref "U8") (pin "24") (pinfunction "SDA_24") (pintype "unspecified"))
    )
    (net (code "26") (name "Net-(USB2-DN1)") (class "Default")
      (node (ref "R6") (pin "1") (pinfunction "1_1") (pintype "input"))
      (node (ref "USB2") (pin "5") (pinfunction "DN2_5") (pintype "unspecified"))
      (node (ref "USB2") (pin "7") (pinfunction "DN1_7") (pintype "unspecified"))
    )
    (net (code "27") (name "Net-(USB2-DP1)") (class "Default")
      (node (ref "R7") (pin "1") (pinfunction "1_1") (pintype "input"))
      (node (ref "USB2") (pin "6") (pinfunction "DP1_6") (pintype "unspecified"))
      (node (ref "USB2") (pin "8") (pinfunction "DP2_8") (pintype "unspecified"))
    )
    (net (code "28") (name "OSC_IN") (class "Default")
      (node (ref "U1") (pin "5") (pinfunction "PH0-OSC_IN_5") (pintype "unspecified"))
      (node (ref "U4") (pin "5") (pinfunction "PH0-OSC_IN_5") (pintype "unspecified"))
      (node (ref "X1") (pin "1") (pinfunction "1_1") (pintype "input"))
      (node (ref "X2") (pin "1") (pinfunction "1_1") (pintype "input"))
    )
    (net (code "29") (name "OSC_OUT") (class "Default")
      (node (ref "U1") (pin "6") (pinfunction "PH1-OSC_OUT_6") (pintype "unspecified"))
      (node (ref "U4") (pin "6") (pinfunction "PH1-OSC_OUT_6") (pintype "unspecified"))
      (node (ref "X1") (pin "3") (pinfunction "3_3") (pintype "input"))
      (node (ref "X2") (pin "3") (pinfunction "3_3") (pintype "input"))
    )
    (net (code "30") (name "PB8") (class "Default")
      (node (ref "U1") (pin "45") (pinfunction "PB8_45") (pintype "unspecified"))
      (node (ref "U2") (pin "23") (pinfunction "SCL_23") (pintype "unspecified"))
      (node (ref "U4") (pin "45") (pinfunction "PB8_45") (pintype "unspecified"))
      (node (ref "U9") (pin "4") (pinfunction "SCK_4") (pintype "unspecified"))
    )
    (net (code "31") (name "PB9") (class "Default")
      (node (ref "U1") (pin "46") (pinfunction "PB9_46") (pintype "unspecified"))
      (node (ref "U2") (pin "24") (pinfunction "SDA_24") (pintype "unspecified"))
      (node (ref "U4") (pin "46") (pinfunction "PB9_46") (pintype "unspecified"))
      (node (ref "U9") (pin "3") (pinfunction "SDI_3") (pintype "unspecified"))
    )
    (net (code "32") (name "SWCLK") (class "Default")
      (node (ref "H1") (pin "1") (pinfunction "1_1") (pintype "unspecified"))
      (node (ref "H3") (pin "1") (pinfunction "1_1") (pintype "unspecified"))
      (node (ref "U1") (pin "37") (pinfunction "PA14_37") (pintype "unspecified"))
      (node (ref "U4") (pin "37") (pinfunction "PA14_37") (pintype "unspecified"))
    )
    (net (code "33") (name "SWDIO") (class "Default")
      (node (ref "H1") (pin "2") (pinfunction "2_2") (pintype "unspecified"))
      (node (ref "H3") (pin "2") (pinfunction "2_2") (pintype "unspecified"))
      (node (ref "U1") (pin "34") (pinfunction "PA13_34") (pintype "unspecified"))
      (node (ref "U4") (pin "34") (pinfunction "PA13_34") (pintype "unspecified"))
    )
    (net (code "34") (name "USB_DM") (class "Default")
      (node (ref "U1") (pin "32") (pinfunction "PA11_32") (pintype "unspecified"))
      (node (ref "U4") (pin "32") (pinfunction "PA11_32") (pintype "unspecified"))
    )
    (net (code "35") (name "USB_DP") (class "Default")
      (node (ref "U1") (pin "33") (pinfunction "PA12_33") (pintype "unspecified"))
      (node (ref "U4") (pin "33") (pinfunction "PA12_33") (pintype "unspecified"))
    )
    (net (code "36") (name "VBAT") (class "Default")
      (node (ref "C16") (pin "1") (pinfunction "1_1") (pintype "unspecified"))
      (node (ref "H2") (pin "1") (pinfunction "1_1") (pintype "unspecified"))
      (node (ref "SW2") (pin "3") (pinfunction "3_3") (pintype "unspecified"))
      (node (ref "U5") (pin "3") (pinfunction "BAT_3") (pintype "unspecified"))
    )
    (net (code "37") (name "VBAT1") (class "Default")
      (node (ref "D1") (pin "2") (pinfunction "A_2") (pintype "unspecified"))
      (node (ref "SW2") (pin "2") (pinfunction "2_2") (pintype "unspecified"))
    )
    (net (code "38") (name "unconnected-(LED3-C-Pad1)") (class "Default")
      (node (ref "LED3") (pin "1") (pinfunction "C_1") (pintype "input"))
    )
    (net (code "39") (name "unconnected-(R6-Pad2)") (class "Default")
      (node (ref "R6") (pin "2") (pinfunction "2_2") (pintype "input"))
    )
    (net (code "40") (name "unconnected-(R7-Pad2)") (class "Default")
      (node (ref "R7") (pin "2") (pinfunction "2_2") (pintype "input"))
    )
    (net (code "41") (name "unconnected-(R13-Pad2)") (class "Default")
      (node (ref "R13") (pin "2") (pinfunction "2_2") (pintype "input"))
    )
    (net (code "42") (name "unconnected-(SW1-Pad3)") (class "Default")
      (node (ref "SW1") (pin "3") (pinfunction "3_3") (pintype "unspecified"))
    )
    (net (code "43") (name "unconnected-(SW2-Pad1)") (class "Default")
      (node (ref "SW2") (pin "1") (pinfunction "1_1") (pintype "unspecified+no_connect"))
    )
    (net (code "44") (name "unconnected-(U1-BOOT0-Pad44)") (class "Default")
      (node (ref "U1") (pin "44") (pinfunction "BOOT0_44") (pintype "unspecified"))
    )
    (net (code "45") (name "unconnected-(U1-EP-Pad49)") (class "Default")
      (node (ref "U1") (pin "49") (pinfunction "EP_49") (pintype "unspecified"))
    )
    (net (code "46") (name "unconnected-(U1-PA0-WKUP-Pad10)") (class "Default")
      (node (ref "U1") (pin "10") (pinfunction "PA0-WKUP_10") (pintype "unspecified"))
    )
    (net (code "47") (name "unconnected-(U1-PA1-Pad11)") (class "Default")
      (node (ref "U1") (pin "11") (pinfunction "PA1_11") (pintype "unspecified"))
    )
    (net (code "48") (name "unconnected-(U1-PA2-Pad12)") (class "Default")
      (node (ref "U1") (pin "12") (pinfunction "PA2_12") (pintype "unspecified"))
    )
    (net (code "49") (name "unconnected-(U1-PA3-Pad13)") (class "Default")
      (node (ref "U1") (pin "13") (pinfunction "PA3_13") (pintype "unspecified"))
    )
    (net (code "50") (name "unconnected-(U1-PA4-Pad14)") (class "Default")
      (node (ref "U1") (pin "14") (pinfunction "PA4_14") (pintype "unspecified"))
    )
    (net (code "51") (name "unconnected-(U1-PA5-Pad15)") (class "Default")
      (node (ref "U1") (pin "15") (pinfunction "PA5_15") (pintype "unspecified"))
    )
    (net (code "52") (name "unconnected-(U1-PA6-Pad16)") (class "Default")
      (node (ref "U1") (pin "16") (pinfunction "PA6_16") (pintype "unspecified"))
    )
    (net (code "53") (name "unconnected-(U1-PA7-Pad17)") (class "Default")
      (node (ref "U1") (pin "17") (pinfunction "PA7_17") (pintype "unspecified"))
    )
    (net (code "54") (name "unconnected-(U1-PA8-Pad29)") (class "Default")
      (node (ref "U1") (pin "29") (pinfunction "PA8_29") (pintype "unspecified"))
    )
    (net (code "55") (name "unconnected-(U1-PA9-Pad30)") (class "Default")
      (node (ref "U1") (pin "30") (pinfunction "PA9_30") (pintype "unspecified"))
    )
    (net (code "56") (name "unconnected-(U1-PA10-Pad31)") (class "Default")
      (node (ref "U1") (pin "31") (pinfunction "PA10_31") (pintype "unspecified"))
    )
    (net (code "57") (name "unconnected-(U1-PA15-Pad38)") (class "Default")
      (node (ref "U1") (pin "38") (pinfunction "PA15_38") (pintype "unspecified"))
    )
    (net (code "58") (name "unconnected-(U1-PB0-Pad18)") (class "Default")
      (node (ref "U1") (pin "18") (pinfunction "PB0_18") (pintype "unspecified"))
    )
    (net (code "59") (name "unconnected-(U1-PB1-Pad19)") (class "Default")
      (node (ref "U1") (pin "19") (pinfunction "PB1_19") (pintype "unspecified"))
    )
    (net (code "60") (name "unconnected-(U1-PB2-Pad20)") (class "Default")
      (node (ref "U1") (pin "20") (pinfunction "PB2_20") (pintype "unspecified"))
    )
    (net (code "61") (name "unconnected-(U1-PB3-Pad39)") (class "Default")
      (node (ref "U1") (pin "39") (pinfunction "PB3_39") (pintype "unspecified"))
    )
    (net (code "62") (name "unconnected-(U1-PB4-Pad40)") (class "Default")
      (node (ref "U1") (pin "40") (pinfunction "PB4_40") (pintype "unspecified"))
    )
    (net (code "63") (name "unconnected-(U1-PB5-Pad41)") (class "Default")
      (node (ref "U1") (pin "41") (pinfunction "PB5_41") (pintype "unspecified"))
    )
    (net (code "64") (name "unconnected-(U1-PB6-Pad42)") (class "Default")
      (node (ref "U1") (pin "42") (pinfunction "PB6_42") (pintype "unspecified"))
    )
    (net (code "65") (name "unconnected-(U1-PB7-Pad43)") (class "Default")
      (node (ref "U1") (pin "43") (pinfunction "PB7_43") (pintype "unspecified"))
    )
    (net (code "66") (name "unconnected-(U1-PB10-Pad21)") (class "Default")
      (node (ref "U1") (pin "21") (pinfunction "PB10_21") (pintype "unspecified"))
    )
    (net (code "67") (name "unconnected-(U1-PB12-Pad25)") (class "Default")
      (node (ref "U1") (pin "25") (pinfunction "PB12_25") (pintype "unspecified"))
    )
    (net (code "68") (name "unconnected-(U1-PB13-Pad26)") (class "Default")
      (node (ref "U1") (pin "26") (pinfunction "PB13_26") (pintype "unspecified"))
    )
    (net (code "69") (name "unconnected-(U1-PB14-Pad27)") (class "Default")
      (node (ref "U1") (pin "27") (pinfunction "PB14_27") (pintype "unspecified"))
    )
    (net (code "70") (name "unconnected-(U1-PB15-Pad28)") (class "Default")
      (node (ref "U1") (pin "28") (pinfunction "PB15_28") (pintype "unspecified"))
    )
    (net (code "71") (name "unconnected-(U1-PC13-ANTI_TAMP-Pad2)") (class "Default")
      (node (ref "U1") (pin "2") (pinfunction "PC13-ANTI_TAMP_2") (pintype "unspecified"))
    )
    (net (code "72") (name "unconnected-(U1-PC14-OSC32_IN-Pad3)") (class "Default")
      (node (ref "U1") (pin "3") (pinfunction "PC14-OSC32_IN_3") (pintype "unspecified"))
    )
    (net (code "73") (name "unconnected-(U1-PC15-OSC32_OUT-Pad4)") (class "Default")
      (node (ref "U1") (pin "4") (pinfunction "PC15-OSC32_OUT_4") (pintype "unspecified"))
    )
    (net (code "74") (name "unconnected-(U1-VDDA{slash}VREF+-Pad9)") (class "Default")
      (node (ref "U1") (pin "9") (pinfunction "VDDA/VREF+_9") (pintype "unspecified"))
    )
    (net (code "75") (name "unconnected-(U1-VSS-Pad47)") (class "Default")
      (node (ref "U1") (pin "47") (pinfunction "VSS_47") (pintype "unspecified"))
    )
    (net (code "76") (name "unconnected-(U1-VSSA{slash}VREF--Pad8)") (class "Default")
      (node (ref "U1") (pin "8") (pinfunction "VSSA/VREF-_8") (pintype "unspecified"))
    )
    (net (code "77") (name "unconnected-(U2-AD0-Pad9)") (class "Default")
      (node (ref "U2") (pin "9") (pinfunction "AD0_9") (pintype "unspecified+no_connect"))
    )
    (net (code "78") (name "unconnected-(U2-AUX_CL-Pad7)") (class "Default")
      (node (ref "U2") (pin "7") (pinfunction "AUX_CL_7") (pintype "unspecified+no_connect"))
    )
    (net (code "79") (name "unconnected-(U2-AUX_DA-Pad6)") (class "Default")
      (node (ref "U2") (pin "6") (pinfunction "AUX_DA_6") (pintype "unspecified+no_connect"))
    )
    (net (code "80") (name "unconnected-(U2-CLKIN-Pad1)") (class "Default")
      (node (ref "U2") (pin "1") (pinfunction "CLKIN_1") (pintype "unspecified+no_connect"))
    )
    (net (code "81") (name "unconnected-(U2-CPOUT-Pad20)") (class "Default")
      (node (ref "U2") (pin "20") (pinfunction "CPOUT_20") (pintype "unspecified+no_connect"))
    )
    (net (code "82") (name "unconnected-(U2-EP-Pad25)") (class "Default")
      (node (ref "U2") (pin "25") (pinfunction "EP_25") (pintype "unspecified+no_connect"))
    )
    (net (code "83") (name "unconnected-(U2-FSYNC-Pad11)") (class "Default")
      (node (ref "U2") (pin "11") (pinfunction "FSYNC_11") (pintype "unspecified+no_connect"))
    )
    (net (code "84") (name "unconnected-(U2-INT-Pad12)") (class "Default")
      (node (ref "U2") (pin "12") (pinfunction "INT_12") (pintype "unspecified+no_connect"))
    )
    (net (code "85") (name "unconnected-(U2-NC-Pad2)") (class "Default")
      (node (ref "U2") (pin "2") (pinfunction "NC_2") (pintype "unspecified+no_connect"))
    )
    (net (code "86") (name "unconnected-(U2-NC-Pad3)") (class "Default")
      (node (ref "U2") (pin "3") (pinfunction "NC_3") (pintype "unspecified+no_connect"))
    )
    (net (code "87") (name "unconnected-(U2-NC-Pad4)") (class "Default")
      (node (ref "U2") (pin "4") (pinfunction "NC_4") (pintype "unspecified+no_connect"))
    )
    (net (code "88") (name "unconnected-(U2-NC-Pad5)") (class "Default")
      (node (ref "U2") (pin "5") (pinfunction "NC_5") (pintype "unspecified+no_connect"))
    )
    (net (code "89") (name "unconnected-(U2-NC-Pad14)") (class "Default")
      (node (ref "U2") (pin "14") (pinfunction "NC_14") (pintype "unspecified+no_connect"))
    )
    (net (code "90") (name "unconnected-(U2-NC-Pad15)") (class "Default")
      (node (ref "U2") (pin "15") (pinfunction "NC_15") (pintype "unspecified+no_connect"))
    )
    (net (code "91") (name "unconnected-(U2-NC-Pad16)") (class "Default")
      (node (ref "U2") (pin "16") (pinfunction "NC_16") (pintype "unspecified+no_connect"))
    )
    (net (code "92") (name "unconnected-(U2-NC-Pad17)") (class "Default")
      (node (ref "U2") (pin "17") (pinfunction "NC_17") (pintype "unspecified+no_connect"))
    )
    (net (code "93") (name "unconnected-(U2-REGOUT-Pad10)") (class "Default")
      (node (ref "U2") (pin "10") (pinfunction "REGOUT_10") (pintype "unspecified+no_connect"))
    )
    (net (code "94") (name "unconnected-(U2-RESV-Pad19)") (class "Default")
      (node (ref "U2") (pin "19") (pinfunction "RESV_19") (pintype "unspecified+no_connect"))
    )
    (net (code "95") (name "unconnected-(U2-RESV-Pad21)") (class "Default")
      (node (ref "U2") (pin "21") (pinfunction "RESV_21") (pintype "unspecified+no_connect"))
    )
    (net (code "96") (name "unconnected-(U2-RESV-Pad22)") (class "Default")
      (node (ref "U2") (pin "22") (pinfunction "RESV_22") (pintype "unspecified+no_connect"))
    )
    (net (code "97") (name "unconnected-(U2-VLOGIC-Pad8)") (class "Default")
      (node (ref "U2") (pin "8") (pinfunction "VLOGIC_8") (pintype "unspecified+no_connect"))
    )
    (net (code "98") (name "unconnected-(U3-CSB-Pad4)") (class "Default")
      (node (ref "U3") (pin "4") (pinfunction "CSB_4") (pintype "unspecified"))
    )
    (net (code "99") (name "unconnected-(U3-CSB-Pad5)") (class "Default")
      (node (ref "U3") (pin "5") (pinfunction "CSB_5") (pintype "unspecified"))
    )
    (net (code "100") (name "unconnected-(U3-GND-Pad3)") (class "Default")
      (node (ref "U3") (pin "3") (pinfunction "GND_3") (pintype "unspecified"))
    )
    (net (code "101") (name "unconnected-(U3-PS-Pad2)") (class "Default")
      (node (ref "U3") (pin "2") (pinfunction "PS_2") (pintype "unspecified"))
    )
    (net (code "102") (name "unconnected-(U3-SCLK-Pad8)") (class "Default")
      (node (ref "U3") (pin "8") (pinfunction "SCLK_8") (pintype "unspecified"))
    )
    (net (code "103") (name "unconnected-(U3-SDI{slash}SDA-Pad7)") (class "Default")
      (node (ref "U3") (pin "7") (pinfunction "SDI/SDA_7") (pintype "unspecified"))
    )
    (net (code "104") (name "unconnected-(U3-SDO-Pad6)") (class "Default")
      (node (ref "U3") (pin "6") (pinfunction "SDO_6") (pintype "unspecified"))
    )
    (net (code "105") (name "unconnected-(U3-VDD-Pad1)") (class "Default")
      (node (ref "U3") (pin "1") (pinfunction "VDD_1") (pintype "unspecified"))
    )
    (net (code "106") (name "unconnected-(U4-BOOT0-Pad44)") (class "Default")
      (node (ref "U4") (pin "44") (pinfunction "BOOT0_44") (pintype "unspecified"))
    )
    (net (code "107") (name "unconnected-(U4-EP-Pad49)") (class "Default")
      (node (ref "U4") (pin "49") (pinfunction "EP_49") (pintype "unspecified"))
    )
    (net (code "108") (name "unconnected-(U4-PA0-WKUP-Pad10)") (class "Default")
      (node (ref "U4") (pin "10") (pinfunction "PA0-WKUP_10") (pintype "unspecified"))
    )
    (net (code "109") (name "unconnected-(U4-PA2-Pad12)") (class "Default")
      (node (ref "U4") (pin "12") (pinfunction "PA2_12") (pintype "unspecified"))
    )
    (net (code "110") (name "unconnected-(U4-PA3-Pad13)") (class "Default")
      (node (ref "U4") (pin "13") (pinfunction "PA3_13") (pintype "unspecified"))
    )
    (net (code "111") (name "unconnected-(U4-PA4-Pad14)") (class "Default")
      (node (ref "U4") (pin "14") (pinfunction "PA4_14") (pintype "unspecified"))
    )
    (net (code "112") (name "unconnected-(U4-PA5-Pad15)") (class "Default")
      (node (ref "U4") (pin "15") (pinfunction "PA5_15") (pintype "unspecified"))
    )
    (net (code "113") (name "unconnected-(U4-PA6-Pad16)") (class "Default")
      (node (ref "U4") (pin "16") (pinfunction "PA6_16") (pintype "unspecified"))
    )
    (net (code "114") (name "unconnected-(U4-PA7-Pad17)") (class "Default")
      (node (ref "U4") (pin "17") (pinfunction "PA7_17") (pintype "unspecified"))
    )
    (net (code "115") (name "unconnected-(U4-PA8-Pad29)") (class "Default")
      (node (ref "U4") (pin "29") (pinfunction "PA8_29") (pintype "unspecified"))
    )
    (net (code "116") (name "unconnected-(U4-PA9-Pad30)") (class "Default")
      (node (ref "U4") (pin "30") (pinfunction "PA9_30") (pintype "unspecified"))
    )
    (net (code "117") (name "unconnected-(U4-PA10-Pad31)") (class "Default")
      (node (ref "U4") (pin "31") (pinfunction "PA10_31") (pintype "unspecified"))
    )
    (net (code "118") (name "unconnected-(U4-PA15-Pad38)") (class "Default")
      (node (ref "U4") (pin "38") (pinfunction "PA15_38") (pintype "unspecified"))
    )
    (net (code "119") (name "unconnected-(U4-PB0-Pad18)") (class "Default")
      (node (ref "U4") (pin "18") (pinfunction "PB0_18") (pintype "unspecified"))
    )
    (net (code "120") (name "unconnected-(U4-PB1-Pad19)") (class "Default")
      (node (ref "U4") (pin "19") (pinfunction "PB1_19") (pintype "unspecified"))
    )
    (net (code "121") (name "unconnected-(U4-PB3-Pad39)") (class "Default")
      (node (ref "U4") (pin "39") (pinfunction "PB3_39") (pintype "unspecified"))
    )
    (net (code "122") (name "unconnected-(U4-PB4-Pad40)") (class "Default")
      (node (ref "U4") (pin "40") (pinfunction "PB4_40") (pintype "unspecified"))
    )
    (net (code "123") (name "unconnected-(U4-PB5-Pad41)") (class "Default")
      (node (ref "U4") (pin "41") (pinfunction "PB5_41") (pintype "unspecified"))
    )
    (net (code "124") (name "unconnected-(U4-PB6-Pad42)") (class "Default")
      (node (ref "U4") (pin "42") (pinfunction "PB6_42") (pintype "unspecified"))
    )
    (net (code "125") (name "unconnected-(U4-PB7-Pad43)") (class "Default")
      (node (ref "U4") (pin "43") (pinfunction "PB7_43") (pintype "unspecified"))
    )
    (net (code "126") (name "unconnected-(U4-PB10-Pad21)") (class "Default")
      (node (ref "U4") (pin "21") (pinfunction "PB10_21") (pintype "unspecified"))
    )
    (net (code "127") (name "unconnected-(U4-PB12-Pad25)") (class "Default")
      (node (ref "U4") (pin "25") (pinfunction "PB12_25") (pintype "unspecified"))
    )
    (net (code "128") (name "unconnected-(U4-PB13-Pad26)") (class "Default")
      (node (ref "U4") (pin "26") (pinfunction "PB13_26") (pintype "unspecified"))
    )
    (net (code "129") (name "unconnected-(U4-PB14-Pad27)") (class "Default")
      (node (ref "U4") (pin "27") (pinfunction "PB14_27") (pintype "unspecified"))
    )
    (net (code "130") (name "unconnected-(U4-PB15-Pad28)") (class "Default")
      (node (ref "U4") (pin "28") (pinfunction "PB15_28") (pintype "unspecified"))
    )
    (net (code "131") (name "unconnected-(U4-PC13-ANTI_TAMP-Pad2)") (class "Default")
      (node (ref "U4") (pin "2") (pinfunction "PC13-ANTI_TAMP_2") (pintype "unspecified"))
    )
    (net (code "132") (name "unconnected-(U4-PC14-OSC32_IN-Pad3)") (class "Default")
      (node (ref "U4") (pin "3") (pinfunction "PC14-OSC32_IN_3") (pintype "unspecified"))
    )
    (net (code "133") (name "unconnected-(U4-PC15-OSC32_OUT-Pad4)") (class "Default")
      (node (ref "U4") (pin "4") (pinfunction "PC15-OSC32_OUT_4") (pintype "unspecified"))
    )
    (net (code "134") (name "unconnected-(U4-VDDA{slash}VREF+-Pad9)") (class "Default")
      (node (ref "U4") (pin "9") (pinfunction "VDDA/VREF+_9") (pintype "unspecified"))
    )
    (net (code "135") (name "unconnected-(U4-VSS-Pad47)") (class "Default")
      (node (ref "U4") (pin "47") (pinfunction "VSS_47") (pintype "unspecified"))
    )
    (net (code "136") (name "unconnected-(U4-VSSA{slash}VREF--Pad8)") (class "Default")
      (node (ref "U4") (pin "8") (pinfunction "VSSA/VREF-_8") (pintype "unspecified"))
    )
    (net (code "137") (name "unconnected-(U6-NC-Pad6)") (class "Default")
      (node (ref "U6") (pin "6") (pinfunction "NC_6") (pintype "unspecified+no_connect"))
    )
    (net (code "138") (name "unconnected-(U8-AUX_CL-Pad7)") (class "Default")
      (node (ref "U8") (pin "7") (pinfunction "AUX_CL_7") (pintype "unspecified+no_connect"))
    )
    (net (code "139") (name "unconnected-(U8-AUX_DA-Pad6)") (class "Default")
      (node (ref "U8") (pin "6") (pinfunction "AUX_DA_6") (pintype "unspecified+no_connect"))
    )
    (net (code "140") (name "unconnected-(U8-EP-Pad25)") (class "Default")
      (node (ref "U8") (pin "25") (pinfunction "EP_25") (pintype "unspecified+no_connect"))
    )
    (net (code "141") (name "unconnected-(U8-INT-Pad12)") (class "Default")
      (node (ref "U8") (pin "12") (pinfunction "INT_12") (pintype "unspecified+no_connect"))
    )
    (net (code "142") (name "unconnected-(U8-NC-Pad2)") (class "Default")
      (node (ref "U8") (pin "2") (pinfunction "NC_2") (pintype "unspecified+no_connect"))
    )
    (net (code "143") (name "unconnected-(U8-NC-Pad3)") (class "Default")
      (node (ref "U8") (pin "3") (pinfunction "NC_3") (pintype "unspecified+no_connect"))
    )
    (net (code "144") (name "unconnected-(U8-NC-Pad4)") (class "Default")
      (node (ref "U8") (pin "4") (pinfunction "NC_4") (pintype "unspecified+no_connect"))
    )
    (net (code "145") (name "unconnected-(U8-NC-Pad5)") (class "Default")
      (node (ref "U8") (pin "5") (pinfunction "NC_5") (pintype "unspecified+no_connect"))
    )
    (net (code "146") (name "unconnected-(U8-NC-Pad14)") (class "Default")
      (node (ref "U8") (pin "14") (pinfunction "NC_14") (pintype "unspecified+no_connect"))
    )
    (net (code "147") (name "unconnected-(U8-NC-Pad15)") (class "Default")
      (node (ref "U8") (pin "15") (pinfunction "NC_15") (pintype "unspecified+no_connect"))
    )
    (net (code "148") (name "unconnected-(U8-NC-Pad16)") (class "Default")
      (node (ref "U8") (pin "16") (pinfunction "NC_16") (pintype "unspecified+no_connect"))
    )
    (net (code "149") (name "unconnected-(U8-NC-Pad17)") (class "Default")
      (node (ref "U8") (pin "17") (pinfunction "NC_17") (pintype "unspecified+no_connect"))
    )
    (net (code "150") (name "unconnected-(U8-RESV-Pad19)") (class "Default")
      (node (ref "U8") (pin "19") (pinfunction "RESV_19") (pintype "unspecified+no_connect"))
    )
    (net (code "151") (name "unconnected-(U8-RESV-Pad21)") (class "Default")
      (node (ref "U8") (pin "21") (pinfunction "RESV_21") (pintype "unspecified+no_connect"))
    )
    (net (code "152") (name "unconnected-(U8-RESV-Pad22)") (class "Default")
      (node (ref "U8") (pin "22") (pinfunction "RESV_22") (pintype "unspecified+no_connect"))
    )
    (net (code "153") (name "unconnected-(USB2-CC1-Pad4)") (class "Default")
      (node (ref "USB2") (pin "4") (pinfunction "CC1_4") (pintype "unspecified+no_connect"))
    )
    (net (code "154") (name "unconnected-(USB2-CC2-Pad10)") (class "Default")
      (node (ref "USB2") (pin "10") (pinfunction "CC2_10") (pintype "unspecified+no_connect"))
    )
    (net (code "155") (name "unconnected-(USB2-SBU1-Pad9)") (class "Default")
      (node (ref "USB2") (pin "9") (pinfunction "SBU1_9") (pintype "unspecified+no_connect"))
    )
    (net (code "156") (name "unconnected-(USB2-SBU2-Pad3)") (class "Default")
      (node (ref "USB2") (pin "3") (pinfunction "SBU2_3") (pintype "unspecified+no_connect"))
    )
  )
)
